# Capteur.net
KiCad netlist of a schematic drawn in Altium Designer
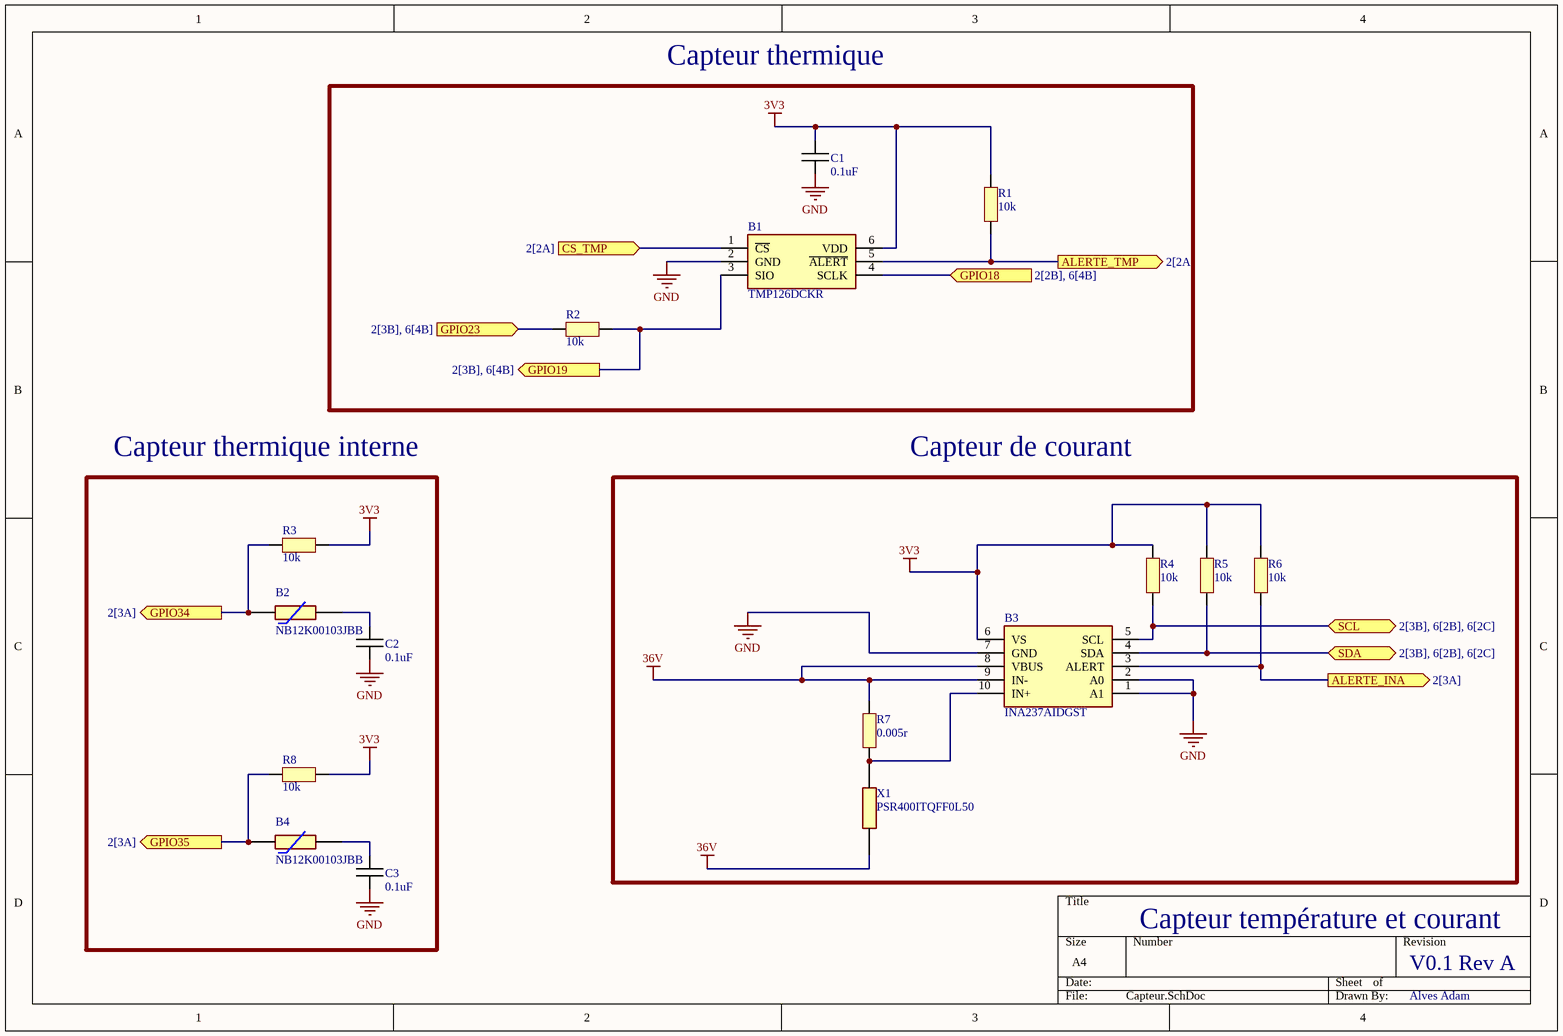
[diagram p0: Capteur.SchDoc]

(export (version "E")
  (design (tool "Eeschema 10.0.6"))
  (components
    (comp (ref "B1")
      (value "TMP126DCKR")
      (footprint "SOT65P210X110-6N")
      (fields (field (name "MOUSER PART NUMBER") "595-TMP126DCKR"))
      (libsource (lib "SCHLibrary") (part "TMP126DCKR"))
    )
    (comp (ref "B2")
      (value "NB12K00103JBB")
      (footprint "RESC2212X50N")
      (description "NTC SMD Thermistor, NB12K, 10K, 5% AVX 10k 0805 Protection NTC Thermistor, 5s, 2 x 1.25 x 1.3mm")
      (fields (field (name "MOUSER PART NUMBER") "581-NB12K00103JBB"))
      (libsource (lib "SCHLibrary") (part "NB12K00103JBB"))
    )
    (comp (ref "B3")
      (value "INA237AIDGST")
      (footprint "SOP50P490X110-10N")
      (fields (field (name "MOUSER PART NUMBER") "595-INA237AIDGST"))
      (libsource (lib "SCHLibrary") (part "INA237AIDGST"))
    )
    (comp (ref "B4")
      (value "NB12K00103JBB")
      (footprint "RESC2212X50N")
      (description "NTC SMD Thermistor, NB12K, 10K, 5% AVX 10k 0805 Protection NTC Thermistor, 5s, 2 x 1.25 x 1.3mm")
      (fields (field (name "MOUSER PART NUMBER") "581-NB12K00103JBB"))
      (libsource (lib "SCHLibrary") (part "NB12K00103JBB"))
    )
    (comp (ref "C1")
      (value "0.1uF")
      (footprint "CAPC1005X06N")
      (libsource (lib "SCHLibrary") (part "Capacitor"))
    )
    (comp (ref "C2")
      (value "0.1uF")
      (footprint "CAPC1005X06N")
      (libsource (lib "SCHLibrary") (part "Capacitor"))
    )
    (comp (ref "C3")
      (value "0.1uF")
      (footprint "CAPC1005X06N")
      (libsource (lib "SCHLibrary") (part "Capacitor"))
    )
    (comp (ref "R1") (value "10k") (footprint "RESC1005X06N") (libsource (lib "") (part "Resistor_1")))
    (comp (ref "R2") (value "10k") (footprint "RESC1005X06N") (libsource (lib "") (part "Resistor_2")))
    (comp (ref "R3") (value "10k") (footprint "RESC1005X06N") (libsource (lib "") (part "Resistor_2")))
    (comp (ref "R4")
      (value "10k")
      (footprint "RESC1005X06N")
      (libsource (lib "SCHLibrary") (part "Resistor"))
    )
    (comp (ref "R5")
      (value "10k")
      (footprint "RESC1005X06N")
      (libsource (lib "SCHLibrary") (part "Resistor"))
    )
    (comp (ref "R6")
      (value "10k")
      (footprint "RESC1005X06N")
      (libsource (lib "SCHLibrary") (part "Resistor"))
    )
    (comp (ref "R7")
      (value "0.005r")
      (footprint "RESC1005X06N")
      (libsource (lib "SCHLibrary") (part "Resistor"))
    )
    (comp (ref "R8") (value "10k") (footprint "RESC1005X06N") (libsource (lib "") (part "Resistor_2")))
    (comp (ref "X1")
      (value "PSR400ITQFF0L50")
      (footprint "RESC10052X200N")
      (fields (field (name "MOUSER PART NUMBER") "755-PSR400ITQFF0L50"))
      (libsource (lib "SCHLibrary") (part "PSR400ITQFF0L50"))
    )
  )
  (nets
    (net (code "1") (name "/ALERTE_INA") (class "Default")
      (node (ref "B3") (pin "3") (pinfunction "ALERT_3") (pintype "passive"))
      (node (ref "R6") (pin "1") (pinfunction "1_1") (pintype "passive"))
    )
    (net (code "2") (name "/ALERTE_TMP") (class "Default")
      (node (ref "B1") (pin "5") (pinfunction "~{ALERT}_5") (pintype "passive"))
      (node (ref "R1") (pin "2") (pinfunction "2_2") (pintype "passive"))
    )
    (net (code "3") (name "/CS_TMP") (class "Default")
      (node (ref "B1") (pin "1") (pinfunction "~{CS}_1") (pintype "passive"))
    )
    (net (code "4") (name "/GPIO18") (class "Default")
      (node (ref "B1") (pin "4") (pinfunction "SCLK_4") (pintype "passive"))
    )
    (net (code "5") (name "/GPIO19") (class "Default")
      (node (ref "B1") (pin "3") (pinfunction "SIO_3") (pintype "passive"))
      (node (ref "R2") (pin "2") (pinfunction "2_2") (pintype "passive"))
    )
    (net (code "6") (name "/GPIO23") (class "Default")
      (node (ref "R2") (pin "1") (pinfunction "1_1") (pintype "passive"))
    )
    (net (code "7") (name "/GPIO34") (class "Default")
      (node (ref "B2") (pin "1") (pinfunction "1_1") (pintype "passive"))
      (node (ref "R3") (pin "1") (pinfunction "1_1") (pintype "passive"))
    )
    (net (code "8") (name "/GPIO35") (class "Default")
      (node (ref "B4") (pin "1") (pinfunction "1_1") (pintype "passive"))
      (node (ref "R8") (pin "1") (pinfunction "1_1") (pintype "passive"))
    )
    (net (code "9") (name "/SCL") (class "Default")
      (node (ref "B3") (pin "5") (pinfunction "SCL_5") (pintype "passive"))
      (node (ref "R4") (pin "1") (pinfunction "1_1") (pintype "passive"))
    )
    (net (code "10") (name "/SDA") (class "Default")
      (node (ref "B3") (pin "4") (pinfunction "SDA_4") (pintype "passive"))
      (node (ref "R5") (pin "1") (pinfunction "1_1") (pintype "passive"))
    )
    (net (code "11") (name "3V3") (class "Default")
      (node (ref "B1") (pin "6") (pinfunction "VDD_6") (pintype "passive"))
      (node (ref "B3") (pin "6") (pinfunction "VS_6") (pintype "passive"))
      (node (ref "C1") (pin "1") (pinfunction "1_1") (pintype "passive"))
      (node (ref "R1") (pin "1") (pinfunction "1_1") (pintype "passive"))
      (node (ref "R3") (pin "2") (pinfunction "2_2") (pintype "passive"))
      (node (ref "R4") (pin "2") (pinfunction "2_2") (pintype "passive"))
      (node (ref "R5") (pin "2") (pinfunction "2_2") (pintype "passive"))
      (node (ref "R6") (pin "2") (pinfunction "2_2") (pintype "passive"))
      (node (ref "R8") (pin "2") (pinfunction "2_2") (pintype "passive"))
    )
    (net (code "12") (name "36V") (class "Default")
      (node (ref "B3") (pin "8") (pinfunction "VBUS_8") (pintype "passive"))
      (node (ref "B3") (pin "9") (pinfunction "IN-_9") (pintype "passive"))
      (node (ref "R7") (pin "2") (pinfunction "2_2") (pintype "passive"))
      (node (ref "X1") (pin "1") (pinfunction "1_1") (pintype "passive"))
    )
    (net (code "13") (name "GND") (class "Default")
      (node (ref "B1") (pin "2") (pinfunction "GND_2") (pintype "passive"))
      (node (ref "B3") (pin "1") (pinfunction "A1_1") (pintype "passive"))
      (node (ref "B3") (pin "2") (pinfunction "A0_2") (pintype "passive"))
      (node (ref "B3") (pin "7") (pinfunction "GND_7") (pintype "passive"))
      (node (ref "C1") (pin "2") (pinfunction "2_2") (pintype "passive"))
      (node (ref "C2") (pin "2") (pinfunction "2_2") (pintype "passive"))
      (node (ref "C3") (pin "2") (pinfunction "2_2") (pintype "passive"))
    )
    (net (code "14") (name "Net-(B2-Pad2)") (class "Default")
      (node (ref "B2") (pin "2") (pinfunction "2_2") (pintype "passive"))
      (node (ref "C2") (pin "1") (pinfunction "1_1") (pintype "passive"))
    )
    (net (code "15") (name "Net-(B3-IN+)") (class "Default")
      (node (ref "B3") (pin "10") (pinfunction "IN+_10") (pintype "passive"))
      (node (ref "R7") (pin "1") (pinfunction "1_1") (pintype "passive"))
      (node (ref "X1") (pin "2") (pinfunction "2_2") (pintype "passive"))
    )
    (net (code "16") (name "Net-(B4-Pad2)") (class "Default")
      (node (ref "B4") (pin "2") (pinfunction "2_2") (pintype "passive"))
      (node (ref "C3") (pin "1") (pinfunction "1_1") (pintype "passive"))
    )
  )
)
